# SampleCtrl.net
KiCad netlist of a schematic drawn in Altium Designer
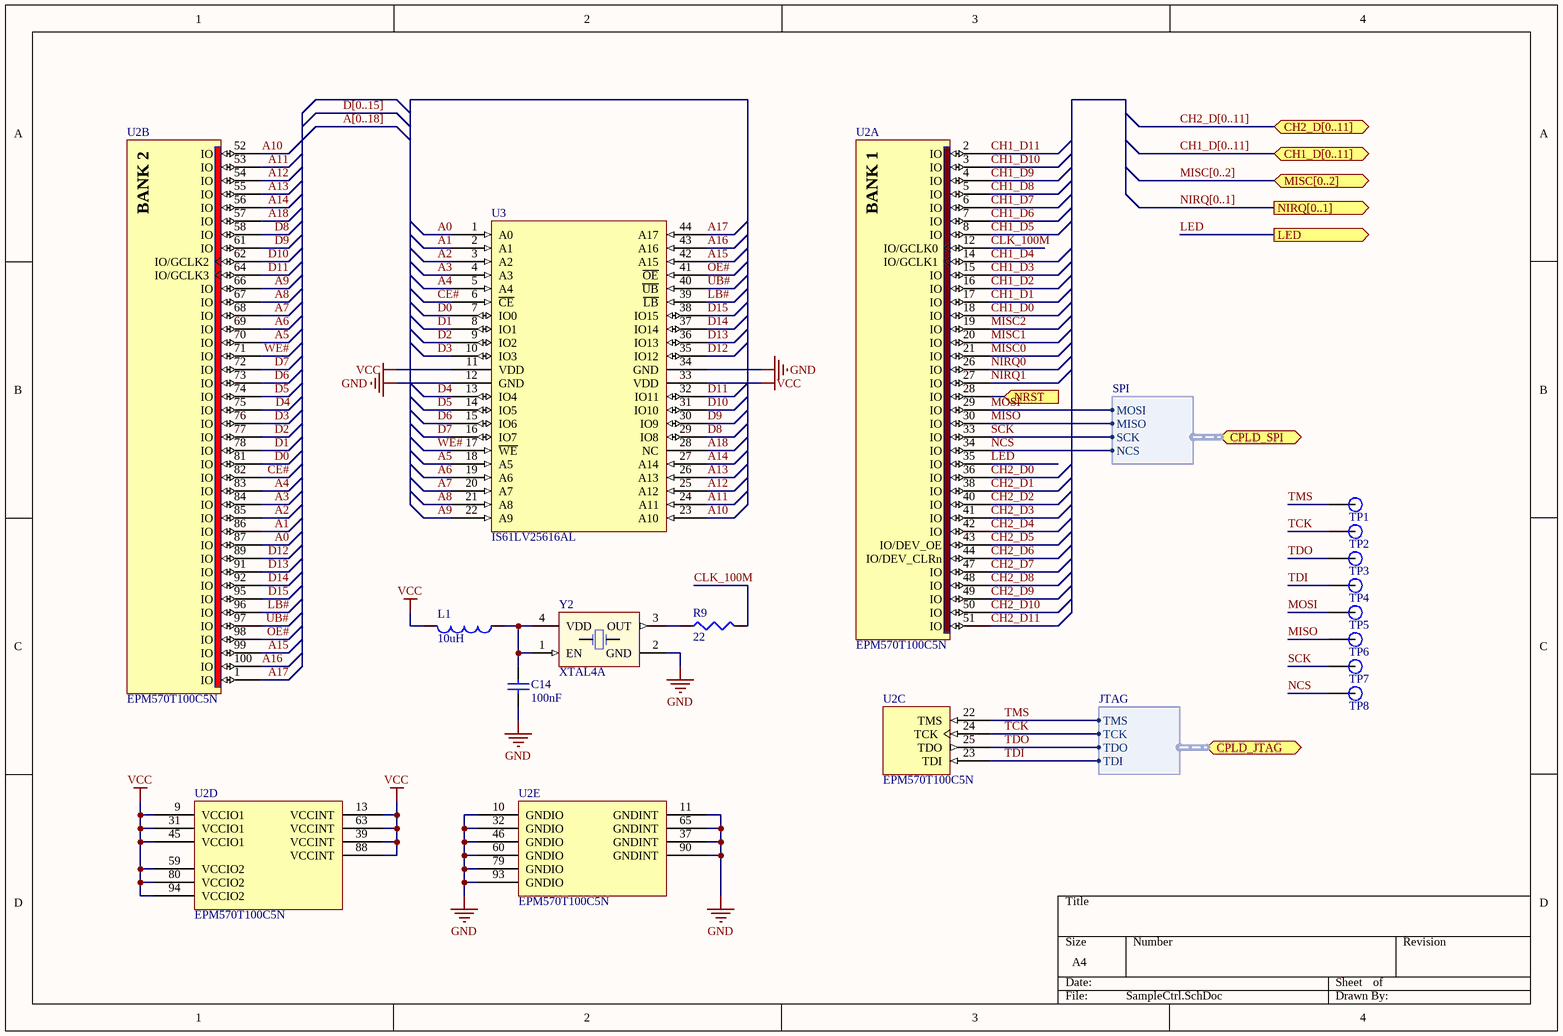
[diagram p0: SampleCtrl.SchDoc]

(export (version "E")
  (design (tool "Eeschema 10.0.6"))
  (components
    (comp (ref "C14")
      (value "100nF")
      (footprint "0603C")
      (description "Capacitor")
      (fields (field (name "Comment") "Cap") (field (name "PUBLISHER") "Altium Limited"))
      (libsource (lib "Miscellaneous Devices") (part "Cap"))
    )
    (comp (ref "L1")
      (value "10uH")
      (footprint "0805L")
      (description "Inductor")
      (fields (field (name "PUBLISHER") "Altium Limited"))
      (libsource (lib "Miscellaneous Devices") (part "Inductor"))
    )
    (comp (ref "R9")
      (value "22")
      (footprint "0603R")
      (description "Resistor")
      (fields (field (name "Comment") "Res3") (field (name "PUBLISHER") "Altium Limited"))
      (libsource (lib "Miscellaneous Devices") (part "Res3"))
    )
    (comp (ref "TP1")
      (value "TestPoint")
      (footprint "TPOINT-30")
      (description "测试点")
      (libsource (lib "WiDSO") (part "TestPoint"))
    )
    (comp (ref "TP2")
      (value "TestPoint")
      (footprint "TPOINT-30")
      (description "测试点")
      (libsource (lib "WiDSO") (part "TestPoint"))
    )
    (comp (ref "TP3")
      (value "TestPoint")
      (footprint "TPOINT-30")
      (description "测试点")
      (libsource (lib "WiDSO") (part "TestPoint"))
    )
    (comp (ref "TP4")
      (value "TestPoint")
      (footprint "TPOINT-30")
      (description "测试点")
      (libsource (lib "WiDSO") (part "TestPoint"))
    )
    (comp (ref "TP5")
      (value "TestPoint")
      (footprint "TPOINT-30")
      (description "测试点")
      (libsource (lib "WiDSO") (part "TestPoint"))
    )
    (comp (ref "TP6")
      (value "TestPoint")
      (footprint "TPOINT-30")
      (description "测试点")
      (libsource (lib "WiDSO") (part "TestPoint"))
    )
    (comp (ref "TP7")
      (value "TestPoint")
      (footprint "TPOINT-30")
      (description "测试点")
      (libsource (lib "WiDSO") (part "TestPoint"))
    )
    (comp (ref "TP8")
      (value "TestPoint")
      (footprint "TPOINT-30")
      (description "测试点")
      (libsource (lib "WiDSO") (part "TestPoint"))
    )
    (comp (ref "U2")
      (value "EPM570T100C5N")
      (footprint "TQFP100_N")
      (fields (field (name "PUBLISHER") "Altium Limited"))
      (libsource (lib "Altera MAX II") (part "EPM570T100C5N"))
    )
    (comp (ref "U3")
      (value "IS61LV25616AL")
      (footprint "TSOP-2L")
      (description "256K*16 SRAM, 3.3V")
      (libsource (lib "WiDSO") (part "IS61LV25616AL"))
    )
    (comp (ref "Y2")
      (value "XTAL4A")
      (footprint "XTAL_7050_4P")
      (description "4脚有源晶振")
      (libsource (lib "WiDSO") (part "XTAL4A"))
    )
  )
  (nets
    (net (code "3") (name "/A0") (class "Default")
      (node (ref "U2") (pin "87") (pinfunction "IO_87") (pintype "bidirectional"))
      (node (ref "U3") (pin "1") (pinfunction "A0_1") (pintype "input"))
    )
    (net (code "4") (name "/A1") (class "Default")
      (node (ref "U2") (pin "86") (pinfunction "IO_86") (pintype "bidirectional"))
      (node (ref "U3") (pin "2") (pinfunction "A1_2") (pintype "input"))
    )
    (net (code "5") (name "/A2") (class "Default")
      (node (ref "U2") (pin "85") (pinfunction "IO_85") (pintype "bidirectional"))
      (node (ref "U3") (pin "3") (pinfunction "A2_3") (pintype "input"))
    )
    (net (code "6") (name "/A3") (class "Default")
      (node (ref "U2") (pin "84") (pinfunction "IO_84") (pintype "bidirectional"))
      (node (ref "U3") (pin "4") (pinfunction "A3_4") (pintype "input"))
    )
    (net (code "7") (name "/A4") (class "Default")
      (node (ref "U2") (pin "83") (pinfunction "IO_83") (pintype "bidirectional"))
      (node (ref "U3") (pin "5") (pinfunction "A4_5") (pintype "input"))
    )
    (net (code "8") (name "/A5") (class "Default")
      (node (ref "U2") (pin "70") (pinfunction "IO_70") (pintype "bidirectional"))
      (node (ref "U3") (pin "18") (pinfunction "A5_18") (pintype "input"))
    )
    (net (code "9") (name "/A6") (class "Default")
      (node (ref "U2") (pin "69") (pinfunction "IO_69") (pintype "bidirectional"))
      (node (ref "U3") (pin "19") (pinfunction "A6_19") (pintype "input"))
    )
    (net (code "10") (name "/A7") (class "Default")
      (node (ref "U2") (pin "68") (pinfunction "IO_68") (pintype "bidirectional"))
      (node (ref "U3") (pin "20") (pinfunction "A7_20") (pintype "input"))
    )
    (net (code "11") (name "/A8") (class "Default")
      (node (ref "U2") (pin "67") (pinfunction "IO_67") (pintype "bidirectional"))
      (node (ref "U3") (pin "21") (pinfunction "A8_21") (pintype "input"))
    )
    (net (code "12") (name "/A9") (class "Default")
      (node (ref "U2") (pin "66") (pinfunction "IO_66") (pintype "bidirectional"))
      (node (ref "U3") (pin "22") (pinfunction "A9_22") (pintype "input"))
    )
    (net (code "13") (name "/A10") (class "Default")
      (node (ref "U2") (pin "52") (pinfunction "IO_52") (pintype "bidirectional"))
      (node (ref "U3") (pin "23") (pinfunction "A10_23") (pintype "input"))
    )
    (net (code "14") (name "/A11") (class "Default")
      (node (ref "U2") (pin "53") (pinfunction "IO_53") (pintype "bidirectional"))
      (node (ref "U3") (pin "24") (pinfunction "A11_24") (pintype "input"))
    )
    (net (code "15") (name "/A12") (class "Default")
      (node (ref "U2") (pin "54") (pinfunction "IO_54") (pintype "bidirectional"))
      (node (ref "U3") (pin "25") (pinfunction "A12_25") (pintype "input"))
    )
    (net (code "16") (name "/A13") (class "Default")
      (node (ref "U2") (pin "55") (pinfunction "IO_55") (pintype "bidirectional"))
      (node (ref "U3") (pin "26") (pinfunction "A13_26") (pintype "input"))
    )
    (net (code "17") (name "/A14") (class "Default")
      (node (ref "U2") (pin "56") (pinfunction "IO_56") (pintype "bidirectional"))
      (node (ref "U3") (pin "27") (pinfunction "A14_27") (pintype "input"))
    )
    (net (code "18") (name "/A15") (class "Default")
      (node (ref "U2") (pin "99") (pinfunction "IO_99") (pintype "bidirectional"))
      (node (ref "U3") (pin "42") (pinfunction "A15_42") (pintype "input"))
    )
    (net (code "19") (name "/A16") (class "Default")
      (node (ref "U2") (pin "100") (pinfunction "IO_100") (pintype "bidirectional"))
      (node (ref "U3") (pin "43") (pinfunction "A16_43") (pintype "input"))
    )
    (net (code "20") (name "/A17") (class "Default")
      (node (ref "U2") (pin "1") (pinfunction "IO_1") (pintype "bidirectional"))
      (node (ref "U3") (pin "44") (pinfunction "A17_44") (pintype "input"))
    )
    (net (code "21") (name "/A18") (class "Default")
      (node (ref "U2") (pin "57") (pinfunction "IO_57") (pintype "bidirectional"))
      (node (ref "U3") (pin "28") (pinfunction "NC_28") (pintype "passive"))
    )
    (net (code "23") (name "/CE#") (class "Default")
      (node (ref "U2") (pin "82") (pinfunction "IO_82") (pintype "bidirectional"))
      (node (ref "U3") (pin "6") (pinfunction "~{CE}_6") (pintype "input"))
    )
    (net (code "24") (name "/CH1_D0") (class "Default")
      (node (ref "U2") (pin "18") (pinfunction "IO_18") (pintype "bidirectional"))
    )
    (net (code "25") (name "/CH1_D1") (class "Default")
      (node (ref "U2") (pin "17") (pinfunction "IO_17") (pintype "bidirectional"))
    )
    (net (code "26") (name "/CH1_D2") (class "Default")
      (node (ref "U2") (pin "16") (pinfunction "IO_16") (pintype "bidirectional"))
    )
    (net (code "27") (name "/CH1_D3") (class "Default")
      (node (ref "U2") (pin "15") (pinfunction "IO_15") (pintype "bidirectional"))
    )
    (net (code "28") (name "/CH1_D4") (class "Default")
      (node (ref "U2") (pin "14") (pinfunction "IO/GCLK1_14") (pintype "bidirectional"))
    )
    (net (code "29") (name "/CH1_D5") (class "Default")
      (node (ref "U2") (pin "8") (pinfunction "IO_8") (pintype "bidirectional"))
    )
    (net (code "30") (name "/CH1_D6") (class "Default")
      (node (ref "U2") (pin "7") (pinfunction "IO_7") (pintype "bidirectional"))
    )
    (net (code "31") (name "/CH1_D7") (class "Default")
      (node (ref "U2") (pin "6") (pinfunction "IO_6") (pintype "bidirectional"))
    )
    (net (code "32") (name "/CH1_D8") (class "Default")
      (node (ref "U2") (pin "5") (pinfunction "IO_5") (pintype "bidirectional"))
    )
    (net (code "33") (name "/CH1_D9") (class "Default")
      (node (ref "U2") (pin "4") (pinfunction "IO_4") (pintype "bidirectional"))
    )
    (net (code "34") (name "/CH1_D10") (class "Default")
      (node (ref "U2") (pin "3") (pinfunction "IO_3") (pintype "bidirectional"))
    )
    (net (code "35") (name "/CH1_D11") (class "Default")
      (node (ref "U2") (pin "2") (pinfunction "IO_2") (pintype "bidirectional"))
    )
    (net (code "37") (name "/CH2_D0") (class "Default")
      (node (ref "U2") (pin "36") (pinfunction "IO_36") (pintype "bidirectional"))
    )
    (net (code "38") (name "/CH2_D1") (class "Default")
      (node (ref "U2") (pin "38") (pinfunction "IO_38") (pintype "bidirectional"))
    )
    (net (code "39") (name "/CH2_D2") (class "Default")
      (node (ref "U2") (pin "40") (pinfunction "IO_40") (pintype "bidirectional"))
    )
    (net (code "40") (name "/CH2_D3") (class "Default")
      (node (ref "U2") (pin "41") (pinfunction "IO_41") (pintype "bidirectional"))
    )
    (net (code "41") (name "/CH2_D4") (class "Default")
      (node (ref "U2") (pin "42") (pinfunction "IO_42") (pintype "bidirectional"))
    )
    (net (code "42") (name "/CH2_D5") (class "Default")
      (node (ref "U2") (pin "43") (pinfunction "IO/DEV_OE_43") (pintype "bidirectional"))
    )
    (net (code "43") (name "/CH2_D6") (class "Default")
      (node (ref "U2") (pin "44") (pinfunction "IO/DEV_CLRn_44") (pintype "bidirectional"))
    )
    (net (code "44") (name "/CH2_D7") (class "Default")
      (node (ref "U2") (pin "47") (pinfunction "IO_47") (pintype "bidirectional"))
    )
    (net (code "45") (name "/CH2_D8") (class "Default")
      (node (ref "U2") (pin "48") (pinfunction "IO_48") (pintype "bidirectional"))
    )
    (net (code "46") (name "/CH2_D9") (class "Default")
      (node (ref "U2") (pin "49") (pinfunction "IO_49") (pintype "bidirectional"))
    )
    (net (code "47") (name "/CH2_D10") (class "Default")
      (node (ref "U2") (pin "50") (pinfunction "IO_50") (pintype "bidirectional"))
    )
    (net (code "48") (name "/CH2_D11") (class "Default")
      (node (ref "U2") (pin "51") (pinfunction "IO_51") (pintype "bidirectional"))
    )
    (net (code "50") (name "/CLK_100M") (class "Default")
      (node (ref "R9") (pin "2") (pinfunction "2_2") (pintype "passive"))
      (node (ref "U2") (pin "12") (pinfunction "IO/GCLK0_12") (pintype "bidirectional"))
    )
    (net (code "51") (name "/D0") (class "Default")
      (node (ref "U2") (pin "81") (pinfunction "IO_81") (pintype "bidirectional"))
      (node (ref "U3") (pin "7") (pinfunction "IO0_7") (pintype "bidirectional"))
    )
    (net (code "52") (name "/D1") (class "Default")
      (node (ref "U2") (pin "78") (pinfunction "IO_78") (pintype "bidirectional"))
      (node (ref "U3") (pin "8") (pinfunction "IO1_8") (pintype "bidirectional"))
    )
    (net (code "53") (name "/D2") (class "Default")
      (node (ref "U2") (pin "77") (pinfunction "IO_77") (pintype "bidirectional"))
      (node (ref "U3") (pin "9") (pinfunction "IO2_9") (pintype "bidirectional"))
    )
    (net (code "54") (name "/D3") (class "Default")
      (node (ref "U2") (pin "76") (pinfunction "IO_76") (pintype "bidirectional"))
      (node (ref "U3") (pin "10") (pinfunction "IO3_10") (pintype "bidirectional"))
    )
    (net (code "55") (name "/D4") (class "Default")
      (node (ref "U2") (pin "75") (pinfunction "IO_75") (pintype "bidirectional"))
      (node (ref "U3") (pin "13") (pinfunction "IO4_13") (pintype "bidirectional"))
    )
    (net (code "56") (name "/D5") (class "Default")
      (node (ref "U2") (pin "74") (pinfunction "IO_74") (pintype "bidirectional"))
      (node (ref "U3") (pin "14") (pinfunction "IO5_14") (pintype "bidirectional"))
    )
    (net (code "57") (name "/D6") (class "Default")
      (node (ref "U2") (pin "73") (pinfunction "IO_73") (pintype "bidirectional"))
      (node (ref "U3") (pin "15") (pinfunction "IO6_15") (pintype "bidirectional"))
    )
    (net (code "58") (name "/D7") (class "Default")
      (node (ref "U2") (pin "72") (pinfunction "IO_72") (pintype "bidirectional"))
      (node (ref "U3") (pin "16") (pinfunction "IO7_16") (pintype "bidirectional"))
    )
    (net (code "59") (name "/D8") (class "Default")
      (node (ref "U2") (pin "58") (pinfunction "IO_58") (pintype "bidirectional"))
      (node (ref "U3") (pin "29") (pinfunction "IO8_29") (pintype "bidirectional"))
    )
    (net (code "60") (name "/D9") (class "Default")
      (node (ref "U2") (pin "61") (pinfunction "IO_61") (pintype "bidirectional"))
      (node (ref "U3") (pin "30") (pinfunction "IO9_30") (pintype "bidirectional"))
    )
    (net (code "61") (name "/D10") (class "Default")
      (node (ref "U2") (pin "62") (pinfunction "IO/GCLK2_62") (pintype "bidirectional"))
      (node (ref "U3") (pin "31") (pinfunction "IO10_31") (pintype "bidirectional"))
    )
    (net (code "62") (name "/D11") (class "Default")
      (node (ref "U2") (pin "64") (pinfunction "IO/GCLK3_64") (pintype "bidirectional"))
      (node (ref "U3") (pin "32") (pinfunction "IO11_32") (pintype "bidirectional"))
    )
    (net (code "63") (name "/D12") (class "Default")
      (node (ref "U2") (pin "89") (pinfunction "IO_89") (pintype "bidirectional"))
      (node (ref "U3") (pin "35") (pinfunction "IO12_35") (pintype "bidirectional"))
    )
    (net (code "64") (name "/D13") (class "Default")
      (node (ref "U2") (pin "91") (pinfunction "IO_91") (pintype "bidirectional"))
      (node (ref "U3") (pin "36") (pinfunction "IO13_36") (pintype "bidirectional"))
    )
    (net (code "65") (name "/D14") (class "Default")
      (node (ref "U2") (pin "92") (pinfunction "IO_92") (pintype "bidirectional"))
      (node (ref "U3") (pin "37") (pinfunction "IO14_37") (pintype "bidirectional"))
    )
    (net (code "66") (name "/D15") (class "Default")
      (node (ref "U2") (pin "95") (pinfunction "IO_95") (pintype "bidirectional"))
      (node (ref "U3") (pin "38") (pinfunction "IO15_38") (pintype "bidirectional"))
    )
    (net (code "68") (name "/LB#") (class "Default")
      (node (ref "U2") (pin "96") (pinfunction "IO_96") (pintype "bidirectional"))
      (node (ref "U3") (pin "39") (pinfunction "~{LB}_39") (pintype "input"))
    )
    (net (code "69") (name "/LED") (class "Default")
      (node (ref "U2") (pin "35") (pinfunction "IO_35") (pintype "bidirectional"))
    )
    (net (code "70") (name "/MISC0") (class "Default")
      (node (ref "U2") (pin "21") (pinfunction "IO_21") (pintype "bidirectional"))
    )
    (net (code "71") (name "/MISC1") (class "Default")
      (node (ref "U2") (pin "20") (pinfunction "IO_20") (pintype "bidirectional"))
    )
    (net (code "72") (name "/MISC2") (class "Default")
      (node (ref "U2") (pin "19") (pinfunction "IO_19") (pintype "bidirectional"))
    )
    (net (code "74") (name "/MISO") (class "Default")
      (node (ref "TP6") (pin "1") (pinfunction "1_1") (pintype "passive"))
      (node (ref "U2") (pin "30") (pinfunction "IO_30") (pintype "bidirectional"))
    )
    (net (code "75") (name "/MOSI") (class "Default")
      (node (ref "TP5") (pin "1") (pinfunction "1_1") (pintype "passive"))
      (node (ref "U2") (pin "29") (pinfunction "IO_29") (pintype "bidirectional"))
    )
    (net (code "76") (name "/NCS") (class "Default")
      (node (ref "TP8") (pin "1") (pinfunction "1_1") (pintype "passive"))
      (node (ref "U2") (pin "34") (pinfunction "IO_34") (pintype "bidirectional"))
    )
    (net (code "77") (name "/NIRQ0") (class "Default")
      (node (ref "U2") (pin "26") (pinfunction "IO_26") (pintype "bidirectional"))
    )
    (net (code "78") (name "/NIRQ1") (class "Default")
      (node (ref "U2") (pin "27") (pinfunction "IO_27") (pintype "bidirectional"))
    )
    (net (code "80") (name "/NRST") (class "Default")
      (node (ref "U2") (pin "28") (pinfunction "IO_28") (pintype "bidirectional"))
    )
    (net (code "81") (name "/OE#") (class "Default")
      (node (ref "U2") (pin "98") (pinfunction "IO_98") (pintype "bidirectional"))
      (node (ref "U3") (pin "41") (pinfunction "~{OE}_41") (pintype "input"))
    )
    (net (code "82") (name "/SCK") (class "Default")
      (node (ref "TP7") (pin "1") (pinfunction "1_1") (pintype "passive"))
      (node (ref "U2") (pin "33") (pinfunction "IO_33") (pintype "bidirectional"))
    )
    (net (code "83") (name "/TCK") (class "Default")
      (node (ref "TP2") (pin "1") (pinfunction "1_1") (pintype "passive"))
      (node (ref "U2") (pin "24") (pinfunction "TCK_24") (pintype "input"))
    )
    (net (code "84") (name "/TDI") (class "Default")
      (node (ref "TP4") (pin "1") (pinfunction "1_1") (pintype "passive"))
      (node (ref "U2") (pin "23") (pinfunction "TDI_23") (pintype "input"))
    )
    (net (code "85") (name "/TDO") (class "Default")
      (node (ref "TP3") (pin "1") (pinfunction "1_1") (pintype "passive"))
      (node (ref "U2") (pin "25") (pinfunction "TDO_25") (pintype "output"))
    )
    (net (code "86") (name "/TMS") (class "Default")
      (node (ref "TP1") (pin "1") (pinfunction "1_1") (pintype "passive"))
      (node (ref "U2") (pin "22") (pinfunction "TMS_22") (pintype "input"))
    )
    (net (code "87") (name "/UB#") (class "Default")
      (node (ref "U2") (pin "97") (pinfunction "IO_97") (pintype "bidirectional"))
      (node (ref "U3") (pin "40") (pinfunction "~{UB}_40") (pintype "input"))
    )
    (net (code "88") (name "/WE#") (class "Default")
      (node (ref "U2") (pin "71") (pinfunction "IO_71") (pintype "bidirectional"))
      (node (ref "U3") (pin "17") (pinfunction "~{WE}_17") (pintype "input"))
    )
    (net (code "91") (name "GND") (class "Default")
      (node (ref "C14") (pin "2") (pinfunction "2_2") (pintype "passive"))
      (node (ref "U2") (pin "10") (pinfunction "GNDIO_10") (pintype "power_in"))
      (node (ref "U2") (pin "11") (pinfunction "GNDINT_11") (pintype "power_in"))
      (node (ref "U2") (pin "32") (pinfunction "GNDIO_32") (pintype "power_in"))
      (node (ref "U2") (pin "37") (pinfunction "GNDINT_37") (pintype "power_in"))
      (node (ref "U2") (pin "46") (pinfunction "GNDIO_46") (pintype "power_in"))
      (node (ref "U2") (pin "60") (pinfunction "GNDIO_60") (pintype "power_in"))
      (node (ref "U2") (pin "65") (pinfunction "GNDINT_65") (pintype "power_in"))
      (node (ref "U2") (pin "79") (pinfunction "GNDIO_79") (pintype "power_in"))
      (node (ref "U2") (pin "90") (pinfunction "GNDINT_90") (pintype "power_in"))
      (node (ref "U2") (pin "93") (pinfunction "GNDIO_93") (pintype "power_in"))
      (node (ref "U3") (pin "12") (pinfunction "GND_12") (pintype "power_in"))
      (node (ref "U3") (pin "34") (pinfunction "GND_34") (pintype "power_in"))
      (node (ref "Y2") (pin "2") (pinfunction "GND_2") (pintype "power_in"))
    )
    (net (code "92") (name "Net-(Y2-EN)") (class "Default")
      (node (ref "C14") (pin "1") (pinfunction "1_1") (pintype "passive"))
      (node (ref "L1") (pin "1") (pinfunction "1_1") (pintype "passive"))
      (node (ref "Y2") (pin "1") (pinfunction "EN_1") (pintype "input"))
      (node (ref "Y2") (pin "4") (pinfunction "VDD_4") (pintype "power_in"))
    )
    (net (code "93") (name "Net-(Y2-OUT)") (class "Default")
      (node (ref "R9") (pin "1") (pinfunction "1_1") (pintype "passive"))
      (node (ref "Y2") (pin "3") (pinfunction "OUT_3") (pintype "output"))
    )
    (net (code "94") (name "VCC") (class "Default")
      (node (ref "L1") (pin "2") (pinfunction "2_2") (pintype "passive"))
      (node (ref "U2") (pin "13") (pinfunction "VCCINT_13") (pintype "power_in"))
      (node (ref "U2") (pin "31") (pinfunction "VCCIO1_31") (pintype "power_in"))
      (node (ref "U2") (pin "39") (pinfunction "VCCINT_39") (pintype "power_in"))
      (node (ref "U2") (pin "45") (pinfunction "VCCIO1_45") (pintype "power_in"))
      (node (ref "U2") (pin "59") (pinfunction "VCCIO2_59") (pintype "power_in"))
      (node (ref "U2") (pin "63") (pinfunction "VCCINT_63") (pintype "power_in"))
      (node (ref "U2") (pin "80") (pinfunction "VCCIO2_80") (pintype "power_in"))
      (node (ref "U2") (pin "88") (pinfunction "VCCINT_88") (pintype "power_in"))
      (node (ref "U2") (pin "9") (pinfunction "VCCIO1_9") (pintype "power_in"))
      (node (ref "U2") (pin "94") (pinfunction "VCCIO2_94") (pintype "power_in"))
      (node (ref "U3") (pin "11") (pinfunction "VDD_11") (pintype "power_in"))
      (node (ref "U3") (pin "33") (pinfunction "VDD_33") (pintype "power_in"))
    )
  )
)
